# VL53L.net
KiCad netlist of a schematic drawn in Altium Designer
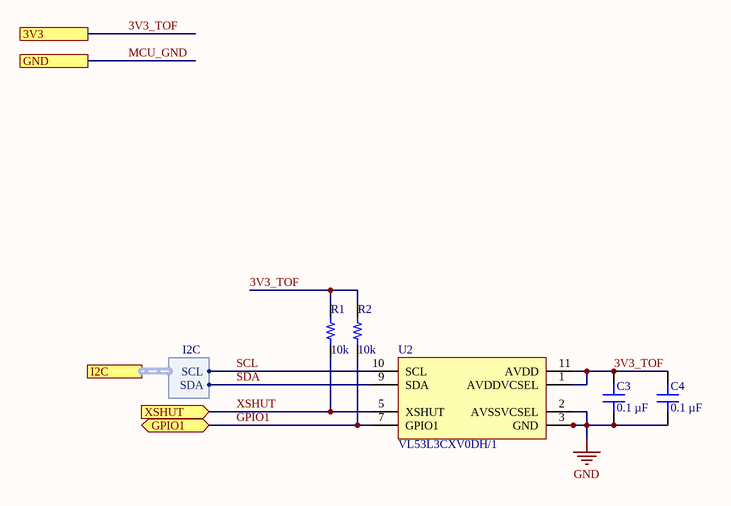
[diagram p0: VL53L.SchDoc]

(export (version "E")
  (design (tool "Eeschema 10.0.6"))
  (components
    (comp (ref "C3")
      (value "0.1 µF")
      (footprint "CAP 0402_1005")
      (description "CAP CER 0.1UF 16V X7R 0402")
      (fields (field (name "PART NUMBER") "C0402C104K4RACAUTO") (field (name "MANUFACTURER") "KEMET"))
      (libsource (lib "Celestial Altium Library - altium_library") (part "Capacitor"))
    )
    (comp (ref "C4")
      (value "0.1 µF")
      (footprint "CAP 0402_1005")
      (description "CAP CER 0.1UF 16V X7R 0402")
      (fields (field (name "PART NUMBER") "C0402C104K4RACAUTO") (field (name "MANUFACTURER") "KEMET"))
      (libsource (lib "Celestial Altium Library - altium_library") (part "Capacitor"))
    )
    (comp (ref "R1")
      (value "10k")
      (footprint "RES 0402_1005")
      (description "RES 330 OHM 5% 1/16W 0402")
      (fields (field (name "PART NUMBER") "CRCW0402330RJNEDC") (field (name "MANUFACTURER") "Vishay Dale"))
      (libsource (lib "Celestial Altium Library - altium_library") (part "Resistor"))
    )
    (comp (ref "R2")
      (value "10k")
      (footprint "RES 0402_1005")
      (description "RES 330 OHM 5% 1/16W 0402")
      (fields (field (name "PART NUMBER") "CRCW0402330RJNEDC") (field (name "MANUFACTURER") "Vishay Dale"))
      (libsource (lib "Celestial Altium Library - altium_library") (part "Resistor"))
    )
    (comp (ref "U2")
      (value "VL53L3CXV0DH/1")
      (footprint "XDCR_VL53L3CXV0DH/1")
      (description "Optical Sensor 118.110 (3m) I2C Output")
      (fields (field (name "MF") "STMicroelectronics"))
      (libsource (lib "IC") (part "VL53L3CXV0DH/1"))
    )
  )
  (nets
    (net (code "2") (name "/3V3_TOF") (class "Default")
      (node (ref "C3") (pin "2") (pinfunction "2_2") (pintype "passive"))
      (node (ref "C4") (pin "2") (pinfunction "2_2") (pintype "passive"))
      (node (ref "R1") (pin "1") (pinfunction "1_1") (pintype "passive"))
      (node (ref "R2") (pin "1") (pinfunction "1_1") (pintype "passive"))
      (node (ref "U2") (pin "1") (pinfunction "AVDDVCSEL_1") (pintype "passive"))
      (node (ref "U2") (pin "11") (pinfunction "AVDD_11") (pintype "passive"))
    )
    (net (code "3") (name "/GPIO1") (class "Default")
      (node (ref "R2") (pin "2") (pinfunction "2_2") (pintype "passive"))
      (node (ref "U2") (pin "7") (pinfunction "GPIO1_7") (pintype "passive"))
    )
    (net (code "4") (name "/SCL") (class "Default")
      (node (ref "U2") (pin "10") (pinfunction "SCL_10") (pintype "passive"))
    )
    (net (code "5") (name "/SDA") (class "Default")
      (node (ref "U2") (pin "9") (pinfunction "SDA_9") (pintype "passive"))
    )
    (net (code "6") (name "/XSHUT") (class "Default")
      (node (ref "R1") (pin "2") (pinfunction "2_2") (pintype "passive"))
      (node (ref "U2") (pin "5") (pinfunction "XSHUT_5") (pintype "passive"))
    )
    (net (code "8") (name "GND") (class "Default")
      (node (ref "C3") (pin "1") (pinfunction "1_1") (pintype "passive"))
      (node (ref "C4") (pin "1") (pinfunction "1_1") (pintype "passive"))
      (node (ref "U2") (pin "12") (pinfunction "GND_12") (pintype "passive"))
      (node (ref "U2") (pin "2") (pinfunction "AVSSVCSEL_2") (pintype "passive"))
      (node (ref "U2") (pin "3") (pinfunction "GND_3") (pintype "power_in"))
      (node (ref "U2") (pin "4") (pinfunction "GND_4") (pintype "power_in"))
      (node (ref "U2") (pin "6") (pinfunction "GND_6") (pintype "power_in"))
    )
  )
)
